# Daughter_Card.net
KiCad netlist of a schematic drawn in Altium Designer
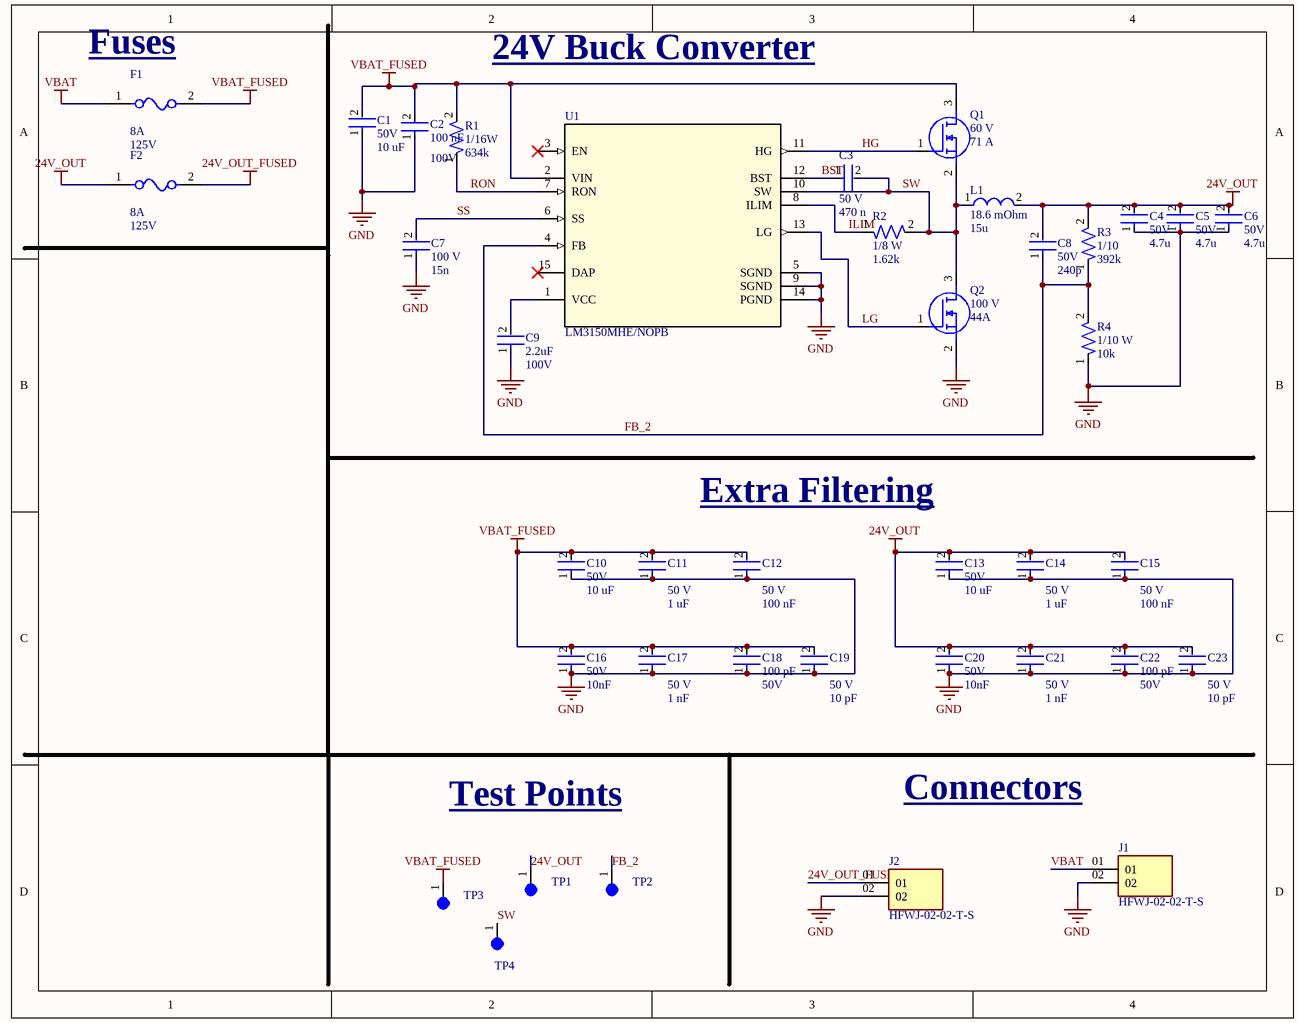
[diagram p0: Daughter_Card.SchDoc]

(export (version "E")
  (design (tool "Eeschema 10.0.6"))
  (components
    (comp (ref "C1")
      (value "CL32B106KBJNNNE")
      (footprint "CAP-1210")
      (description "CAP CER 10UF 50V X7R 1210")
      (fields (field (name "VOLTAGE") "50V") (field (name "CAPACITANCE") "10 uF"))
      (libsource (lib "JLC_25") (part "CAP-10U-0002"))
    )
    (comp (ref "C2")
      (value "GMC10X7S104K100NT")
      (footprint "CAP-0603")
      (description "0.1 µF ±10% 100V Ceramic Capacitor X7S 0603 (1608 Metric)")
      (fields (field (name "CAPACITANCE") "100 nF") (field (name "VOLTAGE") "100V"))
      (libsource (lib "Schlib1") (part "CAP-100N-0001"))
    )
    (comp (ref "C3")
      (value "CC0805ZRY5V9BB474")
      (footprint "CAP-0805")
      (description "0.47 µF -20%, +80% 50V Ceramic Capacitor Y5V (F) 0805 (2012 Metric)")
      (fields (field (name "VOLTAGE") "50 V") (field (name "CAPACITANCE") "470 n"))
      (libsource (lib "JLC_25") (part "CAP-470N-0002"))
    )
    (comp (ref "C4")
      (value "CC1210KFX7R9BB475")
      (footprint "CAP-1210")
      (description "4.7 µF ±10% 50V Ceramic Capacitor X7R 1210 (3225 Metric)")
      (fields (field (name "VOLTAGE") "50V") (field (name "CAPACITANCE") "4.7u"))
      (libsource (lib "JLC_25") (part "CAP-4.7U-0003"))
    )
    (comp (ref "C5")
      (value "CC1210KFX7R9BB475")
      (footprint "CAP-1210")
      (description "4.7 µF ±10% 50V Ceramic Capacitor X7R 1210 (3225 Metric)")
      (fields (field (name "VOLTAGE") "50V") (field (name "CAPACITANCE") "4.7u"))
      (libsource (lib "JLC_25") (part "CAP-4.7U-0003"))
    )
    (comp (ref "C6")
      (value "CC1210KFX7R9BB475")
      (footprint "CAP-1210")
      (description "4.7 µF ±10% 50V Ceramic Capacitor X7R 1210 (3225 Metric)")
      (fields (field (name "VOLTAGE") "50V") (field (name "CAPACITANCE") "4.7u"))
      (libsource (lib "JLC_25") (part "CAP-4.7U-0003"))
    )
    (comp (ref "C7")
      (value "CC0805KRX7R0BB153")
      (footprint "CAP-0805")
      (description "0.015 µF ±10% 100V Ceramic Capacitor X7R 0805 (2012 Metric)")
      (fields (field (name "VOLTAGE") "100 V") (field (name "CAPACITANCE") "15n"))
      (libsource (lib "JLC_25") (part "CAP-15N-0001"))
    )
    (comp (ref "C8")
      (value "CC0402FRNPO9BN241")
      (footprint "CAP-0402")
      (description "240 pF ±1% 50V Ceramic Capacitor C0G, NP0 0402 (1005 Metric)")
      (fields (field (name "VOLTAGE") "50V") (field (name "CAPACITANCE") "240p"))
      (libsource (lib "JLC_25") (part "CAP-240P-0001"))
    )
    (comp (ref "C9")
      (value "CC1206KKX7R0BB225")
      (footprint "CAP-1206")
      (description "CAP CER 2.2UF 100V X7R 1206")
      (fields (field (name "CAPACITANCE") "2.2uF") (field (name "VOLTAGE") "100V"))
      (libsource (lib "JLC_25") (part "CAP-2.2U-0001"))
    )
    (comp (ref "C10")
      (value "CL32B106KBJNNNE")
      (footprint "CAP-1210")
      (description "CAP CER 10UF 50V X7R 1210")
      (fields (field (name "VOLTAGE") "50V") (field (name "CAPACITANCE") "10 uF"))
      (libsource (lib "JLC_25") (part "CAP-10U-0002"))
    )
    (comp (ref "C11")
      (value "CC0805KKX7R9BB105")
      (footprint "CAP-0805")
      (description "1 µF ±10% 50V Ceramic Capacitor X7R 0805 (2012 Metric)")
      (fields (field (name "VOLTAGE") "50 V") (field (name "CAPACITANCE") "1 uF"))
      (libsource (lib "Schlib1") (part "CAP-1U-0001"))
    )
    (comp (ref "C12")
      (value "CC0805KRX7R9BB104")
      (footprint "CAP-0805")
      (description "0.1 µF ±10% 50V Ceramic Capacitor X7R 0805 (2012 Metric)")
      (fields (field (name "VOLTAGE") "50 V") (field (name "CAPACITANCE") "100 nF"))
      (libsource (lib "Schlib1") (part "CAP-100N-0002"))
    )
    (comp (ref "C13")
      (value "CL32B106KBJNNNE")
      (footprint "CAP-1210")
      (description "CAP CER 10UF 50V X7R 1210")
      (fields (field (name "VOLTAGE") "50V") (field (name "CAPACITANCE") "10 uF"))
      (libsource (lib "JLC_25") (part "CAP-10U-0002"))
    )
    (comp (ref "C14")
      (value "CC0805KKX7R9BB105")
      (footprint "CAP-0805")
      (description "1 µF ±10% 50V Ceramic Capacitor X7R 0805 (2012 Metric)")
      (fields (field (name "VOLTAGE") "50 V") (field (name "CAPACITANCE") "1 uF"))
      (libsource (lib "Schlib1") (part "CAP-1U-0001"))
    )
    (comp (ref "C15")
      (value "CC0805KRX7R9BB104")
      (footprint "CAP-0805")
      (description "0.1 µF ±10% 50V Ceramic Capacitor X7R 0805 (2012 Metric)")
      (fields (field (name "VOLTAGE") "50 V") (field (name "CAPACITANCE") "100 nF"))
      (libsource (lib "Schlib1") (part "CAP-100N-0002"))
    )
    (comp (ref "C16")
      (value "GRM2195C1H103JA01D")
      (footprint "CAP-0805")
      (description "CAP CER 10000PF 50V C0G/NP0 0805")
      (fields (field (name "VOLTAGE") "50V") (field (name "CAPACITANCE") "10nF"))
      (libsource (lib "JLC_25") (part "CAP-10N-0001"))
    )
    (comp (ref "C17")
      (value "CC0402KRX7R9BB102")
      (footprint "CAP-0402")
      (description "1000 pF ±10% 50V Ceramic Capacitor X7R 0402 (1005 Metric)")
      (fields (field (name "VOLTAGE") "50 V") (field (name "CAPACITANCE") "1 nF"))
      (libsource (lib "Schlib1") (part "CAP-1N-0001"))
    )
    (comp (ref "C18")
      (value "CC0402JRNPO9BN101")
      (footprint "CAP-0402")
      (description "CAP CER 100PF 50V C0G/NPO 0402")
      (fields (field (name "CAPACITANCE") "100 pF") (field (name "VOLTAGE") "50V"))
      (libsource (lib "JLC_25") (part "CAP-100P-0001"))
    )
    (comp (ref "C19")
      (value "CC0402JRNPO9BN100")
      (footprint "CAP-0402")
      (description "10 pF ±5% 50V Ceramic Capacitor C0G, NP0 0402 (1005 Metric)")
      (fields (field (name "VOLTAGE") "50 V") (field (name "CAPACITANCE") "10 pF"))
      (libsource (lib "Schlib1") (part "CAP-10P-0001"))
    )
    (comp (ref "C20")
      (value "GRM2195C1H103JA01D")
      (footprint "CAP-0805")
      (description "CAP CER 10000PF 50V C0G/NP0 0805")
      (fields (field (name "VOLTAGE") "50V") (field (name "CAPACITANCE") "10nF"))
      (libsource (lib "JLC_25") (part "CAP-10N-0001"))
    )
    (comp (ref "C21")
      (value "CC0402KRX7R9BB102")
      (footprint "CAP-0402")
      (description "1000 pF ±10% 50V Ceramic Capacitor X7R 0402 (1005 Metric)")
      (fields (field (name "VOLTAGE") "50 V") (field (name "CAPACITANCE") "1 nF"))
      (libsource (lib "Schlib1") (part "CAP-1N-0001"))
    )
    (comp (ref "C22")
      (value "CC0402JRNPO9BN101")
      (footprint "CAP-0402")
      (description "CAP CER 100PF 50V C0G/NPO 0402")
      (fields (field (name "CAPACITANCE") "100 pF") (field (name "VOLTAGE") "50V"))
      (libsource (lib "JLC_25") (part "CAP-100P-0001"))
    )
    (comp (ref "C23")
      (value "CC0402JRNPO9BN100")
      (footprint "CAP-0402")
      (description "10 pF ±5% 50V Ceramic Capacitor C0G, NP0 0402 (1005 Metric)")
      (fields (field (name "VOLTAGE") "50 V") (field (name "CAPACITANCE") "10 pF"))
      (libsource (lib "Schlib1") (part "CAP-10P-0001"))
    )
    (comp (ref "F1")
      (value "01550900M")
      (footprint "FUSE-0001")
      (description "FUSE BLOK CARTRIDGE 125V 10A SMD")
      (fields (field (name "FUSE CURRENT") "8A") (field (name "VOLTAGE RATING") "125V"))
      (libsource (lib "JLC_25") (part "FUSE-0001"))
    )
    (comp (ref "F2")
      (value "01550900M")
      (footprint "FUSE-0001")
      (description "FUSE BLOK CARTRIDGE 125V 10A SMD")
      (fields (field (name "FUSE CURRENT") "8A") (field (name "VOLTAGE RATING") "125V"))
      (libsource (lib "JLC_25") (part "FUSE-0001"))
    )
    (comp (ref "J1")
      (value "HFWJ-02-02-T-S")
      (footprint "SAMTEC_HFWJ-02-02-T-S")
      (description "Conn Unshrouded Header HDR 2 POS 3.96mm Solder ST Thru-Hole Bulk")
      (fields (field (name "MF") "Samtec"))
      (libsource (lib "MasterLib") (part "CONN-2POS-0007"))
    )
    (comp (ref "J2")
      (value "HFWJ-02-02-T-S")
      (footprint "SAMTEC_HFWJ-02-02-T-S")
      (description "Conn Unshrouded Header HDR 2 POS 3.96mm Solder ST Thru-Hole Bulk")
      (fields (field (name "MF") "Samtec"))
      (libsource (lib "MasterLib") (part "CONN-2POS-0007"))
    )
    (comp (ref "L1")
      (value "XAL1010-153MED")
      (footprint "IND_XAL1010_COC")
      (description "15 µH Shielded Molded Inductor 9.9 A 18.6mOhm Max Nonstandard")
      (fields
        (field (name "RESISTANCE") "18.6 mOhm")
        (field (name "INDUCTOR") "15u")
        (field (name "COPYRIGHT") "Copyright (C) 2025 Ultra Librarian. All rights reserved.")
      )
      (libsource (lib "MasterLib") (part "IND-15u-0001"))
    )
    (comp (ref "Q1")
      (value "NTMFS5C670NLT1G")
      (footprint "NTMFS5C670NLT1G_ONS - duplicate")
      (description "N-Channel 60 V 17A (Ta), 71A (Tc) 3.6W (Ta), 61W (Tc) Surface Mount 5-DFN (5x6) (8-SOFL)")
      (fields
        (field (name "MAX VOLTAGE") "60 V")
        (field (name "MAX CURRENT") "71 A")
        (field (name "COPYRIGHT") "Copyright (C) 2025 Ultra Librarian. All rights reserved.")
      )
      (libsource (lib "MasterLib") (part "NMOS-71A-0001"))
    )
    (comp (ref "Q2")
      (value "CSD19534Q5A")
      (footprint "TRANS_CSD19534Q5A")
      (description "N-Channel 100 V 44A (Tc) 3.2W (Ta), 63W (Tc) Surface Mount 8-VSONP (5x6)")
      (fields
        (field (name "MF") "Texas Instruments")
        (field (name "VOLTAGE MAX") "100 V")
        (field (name "CURRENT MAX") "44A")
      )
      (libsource (lib "MasterLib") (part "NMOS-44A-0001"))
    )
    (comp (ref "R1")
      (value "RC0402FR-07634KL")
      (footprint "RES-0402")
      (description "634 kOhms ±1% 0.063W, 1/16W Chip Resistor 0402 (1005 Metric) Moisture Resistant Thick Film")
      (fields (field (name "POWER") "1/16W") (field (name "RESISTANCE") "634k"))
      (libsource (lib "JLC_25") (part "RES-634k-0001"))
    )
    (comp (ref "R2")
      (value "RC0805FR-071K62L")
      (footprint "RES-0805")
      (description "1.62 kOhms ±1% 0.125W, 1/8W Chip Resistor 0805 (2012 Metric) Moisture Resistant Thick Film")
      (fields (field (name "POWER") "1/8 W") (field (name "RESISTANCE") "1.62k"))
      (libsource (lib "JLC_25") (part "RES-1.62k-001"))
    )
    (comp (ref "R3")
      (value "RC0603FR-07392KL")
      (footprint "RES-0603")
      (description "392 kOhms ±1% 0.1W, 1/10W Chip Resistor 0603 (1608 Metric) Moisture Resistant Thick Film")
      (fields (field (name "POWER") "1/10") (field (name "RESISTANCE") "392k"))
      (libsource (lib "JLC_25") (part "RES-392k-0001"))
    )
    (comp (ref "R4")
      (value "RC0603FR-0710KL")
      (footprint "CAP-0603")
      (description "10 kOhms ±1% 0.1W, 1/10W Chip Resistor 0603 (1608 Metric) Moisture Resistant Thick Film")
      (fields (field (name "POWER") "1/10 W") (field (name "RESISTANCE") "10k"))
      (libsource (lib "JLC_25") (part "RES-10k-0002"))
    )
    (comp (ref "TP1")
      (value "5003")
      (footprint "TEST-POINT-0001")
      (description "Oranange PC Test Point, Miniature Phoisphor Bronze Silver Plating Through Hole Mounting Type")
      (libsource (lib "JLC_25") (part "TEST-POINT-0001"))
    )
    (comp (ref "TP2")
      (value "5003")
      (footprint "TEST-POINT-0001")
      (description "Oranange PC Test Point, Miniature Phoisphor Bronze Silver Plating Through Hole Mounting Type")
      (libsource (lib "JLC_25") (part "TEST-POINT-0001"))
    )
    (comp (ref "TP3")
      (value "5003")
      (footprint "TEST-POINT-0001")
      (description "Oranange PC Test Point, Miniature Phoisphor Bronze Silver Plating Through Hole Mounting Type")
      (libsource (lib "JLC_25") (part "TEST-POINT-0001"))
    )
    (comp (ref "TP4")
      (value "5003")
      (footprint "TEST-POINT-0001")
      (description "Oranange PC Test Point, Miniature Phoisphor Bronze Silver Plating Through Hole Mounting Type")
      (libsource (lib "JLC_25") (part "TEST-POINT-0001"))
    )
    (comp (ref "U1")
      (value "LM3150MHE/NOPB")
      (footprint "MXA14A")
      (description "6V to 42V Synchronous Step-Down Controller with Adjustable Output Voltage 14-HTSSOP -40 to 125")
      (fields (field (name "COPYRIGHT") "Copyright (C) 2025 Ultra Librarian. All rights reserved."))
      (libsource (lib "MasterLib") (part "IC-BUCK_0011"))
    )
  )
  (nets
    (net (code "1") (name "/BST") (class "Default")
      (node (ref "C3") (pin "1") (pinfunction "1_1") (pintype "passive"))
      (node (ref "U1") (pin "12") (pinfunction "BST_12") (pintype "passive"))
    )
    (net (code "2") (name "/FB_2") (class "Default")
      (node (ref "C8") (pin "1") (pinfunction "1_1") (pintype "passive"))
      (node (ref "R3") (pin "1") (pinfunction "1_1") (pintype "passive"))
      (node (ref "R4") (pin "2") (pinfunction "2_2") (pintype "passive"))
      (node (ref "TP2") (pin "1") (pinfunction "0_1") (pintype "passive"))
      (node (ref "U1") (pin "4") (pinfunction "FB_4") (pintype "input"))
    )
    (net (code "3") (name "/HG") (class "Default")
      (node (ref "Q1") (pin "1") (pinfunction "G_1") (pintype "passive"))
      (node (ref "U1") (pin "11") (pinfunction "HG_11") (pintype "output"))
    )
    (net (code "4") (name "/ILIM") (class "Default")
      (node (ref "R2") (pin "1") (pinfunction "1_1") (pintype "passive"))
      (node (ref "U1") (pin "8") (pinfunction "ILIM_8") (pintype "passive"))
    )
    (net (code "5") (name "/LG") (class "Default")
      (node (ref "Q2") (pin "1") (pinfunction "G_1") (pintype "passive"))
      (node (ref "U1") (pin "13") (pinfunction "LG_13") (pintype "output"))
    )
    (net (code "6") (name "/RON") (class "Default")
      (node (ref "R1") (pin "1") (pinfunction "1_1") (pintype "passive"))
      (node (ref "U1") (pin "7") (pinfunction "RON_7") (pintype "input"))
    )
    (net (code "7") (name "/SS") (class "Default")
      (node (ref "C7") (pin "2") (pinfunction "2_2") (pintype "passive"))
      (node (ref "U1") (pin "6") (pinfunction "SS_6") (pintype "input"))
    )
    (net (code "8") (name "/SW") (class "Default")
      (node (ref "C3") (pin "2") (pinfunction "2_2") (pintype "passive"))
      (node (ref "L1") (pin "1") (pinfunction "1_1") (pintype "passive"))
      (node (ref "Q1") (pin "2") (pinfunction "S_2") (pintype "passive"))
      (node (ref "Q2") (pin "3") (pinfunction "D_3") (pintype "passive"))
      (node (ref "R2") (pin "2") (pinfunction "2_2") (pintype "passive"))
      (node (ref "TP4") (pin "1") (pinfunction "0_1") (pintype "passive"))
      (node (ref "U1") (pin "10") (pinfunction "SW_10") (pintype "power_in"))
    )
    (net (code "9") (name "24V_OUT") (class "Default")
      (node (ref "C13") (pin "2") (pinfunction "2_2") (pintype "passive"))
      (node (ref "C14") (pin "2") (pinfunction "2_2") (pintype "passive"))
      (node (ref "C15") (pin "2") (pinfunction "2_2") (pintype "passive"))
      (node (ref "C20") (pin "2") (pinfunction "2_2") (pintype "passive"))
      (node (ref "C21") (pin "2") (pinfunction "2_2") (pintype "passive"))
      (node (ref "C22") (pin "2") (pinfunction "2_2") (pintype "passive"))
      (node (ref "C23") (pin "2") (pinfunction "2_2") (pintype "passive"))
      (node (ref "C4") (pin "2") (pinfunction "2_2") (pintype "passive"))
      (node (ref "C5") (pin "2") (pinfunction "2_2") (pintype "passive"))
      (node (ref "C6") (pin "2") (pinfunction "2_2") (pintype "passive"))
      (node (ref "C8") (pin "2") (pinfunction "2_2") (pintype "passive"))
      (node (ref "F2") (pin "1") (pinfunction "1_1") (pintype "passive"))
      (node (ref "L1") (pin "2") (pinfunction "2_2") (pintype "passive"))
      (node (ref "R3") (pin "2") (pinfunction "2_2") (pintype "passive"))
      (node (ref "TP1") (pin "1") (pinfunction "0_1") (pintype "passive"))
    )
    (net (code "10") (name "24V_OUT_FUSED") (class "Default")
      (node (ref "F2") (pin "2") (pinfunction "2_2") (pintype "passive"))
      (node (ref "J2") (pin "01") (pinfunction "01_01") (pintype "passive"))
    )
    (net (code "11") (name "GND") (class "Default")
      (node (ref "C1") (pin "1") (pinfunction "1_1") (pintype "passive"))
      (node (ref "C10") (pin "1") (pinfunction "1_1") (pintype "passive"))
      (node (ref "C11") (pin "1") (pinfunction "1_1") (pintype "passive"))
      (node (ref "C12") (pin "1") (pinfunction "1_1") (pintype "passive"))
      (node (ref "C13") (pin "1") (pinfunction "1_1") (pintype "passive"))
      (node (ref "C14") (pin "1") (pinfunction "1_1") (pintype "passive"))
      (node (ref "C15") (pin "1") (pinfunction "1_1") (pintype "passive"))
      (node (ref "C16") (pin "1") (pinfunction "1_1") (pintype "passive"))
      (node (ref "C17") (pin "1") (pinfunction "1_1") (pintype "passive"))
      (node (ref "C18") (pin "1") (pinfunction "1_1") (pintype "passive"))
      (node (ref "C19") (pin "1") (pinfunction "1_1") (pintype "passive"))
      (node (ref "C2") (pin "1") (pinfunction "1_1") (pintype "passive"))
      (node (ref "C20") (pin "1") (pinfunction "1_1") (pintype "passive"))
      (node (ref "C21") (pin "1") (pinfunction "1_1") (pintype "passive"))
      (node (ref "C22") (pin "1") (pinfunction "1_1") (pintype "passive"))
      (node (ref "C23") (pin "1") (pinfunction "1_1") (pintype "passive"))
      (node (ref "C4") (pin "1") (pinfunction "1_1") (pintype "passive"))
      (node (ref "C5") (pin "1") (pinfunction "1_1") (pintype "passive"))
      (node (ref "C6") (pin "1") (pinfunction "1_1") (pintype "passive"))
      (node (ref "C7") (pin "1") (pinfunction "1_1") (pintype "passive"))
      (node (ref "C9") (pin "1") (pinfunction "1_1") (pintype "passive"))
      (node (ref "J1") (pin "02") (pinfunction "02_02") (pintype "passive"))
      (node (ref "J2") (pin "02") (pinfunction "02_02") (pintype "passive"))
      (node (ref "Q2") (pin "2") (pinfunction "S_2") (pintype "passive"))
      (node (ref "R4") (pin "1") (pinfunction "1_1") (pintype "passive"))
      (node (ref "U1") (pin "14") (pinfunction "PGND_14") (pintype "power_in"))
      (node (ref "U1") (pin "5") (pinfunction "SGND_5") (pintype "power_in"))
      (node (ref "U1") (pin "9") (pinfunction "SGND_9") (pintype "power_in"))
    )
    (net (code "12") (name "Net-(U1-VCC)") (class "Default")
      (node (ref "C9") (pin "2") (pinfunction "2_2") (pintype "passive"))
      (node (ref "U1") (pin "1") (pinfunction "VCC_1") (pintype "power_in"))
    )
    (net (code "13") (name "VBAT") (class "Default")
      (node (ref "F1") (pin "1") (pinfunction "1_1") (pintype "passive"))
      (node (ref "J1") (pin "01") (pinfunction "01_01") (pintype "passive"))
    )
    (net (code "14") (name "VBAT_FUSED") (class "Default")
      (node (ref "C1") (pin "2") (pinfunction "2_2") (pintype "passive"))
      (node (ref "C10") (pin "2") (pinfunction "2_2") (pintype "passive"))
      (node (ref "C11") (pin "2") (pinfunction "2_2") (pintype "passive"))
      (node (ref "C12") (pin "2") (pinfunction "2_2") (pintype "passive"))
      (node (ref "C16") (pin "2") (pinfunction "2_2") (pintype "passive"))
      (node (ref "C17") (pin "2") (pinfunction "2_2") (pintype "passive"))
      (node (ref "C18") (pin "2") (pinfunction "2_2") (pintype "passive"))
      (node (ref "C19") (pin "2") (pinfunction "2_2") (pintype "passive"))
      (node (ref "C2") (pin "2") (pinfunction "2_2") (pintype "passive"))
      (node (ref "F1") (pin "2") (pinfunction "2_2") (pintype "passive"))
      (node (ref "Q1") (pin "3") (pinfunction "D_3") (pintype "passive"))
      (node (ref "R1") (pin "2") (pinfunction "2_2") (pintype "passive"))
      (node (ref "TP3") (pin "1") (pinfunction "0_1") (pintype "passive"))
      (node (ref "U1") (pin "2") (pinfunction "VIN_2") (pintype "power_in"))
    )
    (net (code "15") (name "unconnected-(U1-DAP-Pad15)") (class "Default")
      (node (ref "U1") (pin "15") (pinfunction "DAP_15") (pintype "power_in+no_connect"))
    )
    (net (code "16") (name "unconnected-(U1-EN-Pad3)") (class "Default")
      (node (ref "U1") (pin "3") (pinfunction "EN_3") (pintype "input+no_connect"))
    )
  )
)
